# robocon_main_board_2017_rev3.net
KiCad netlist of a schematic drawn in EAGLE
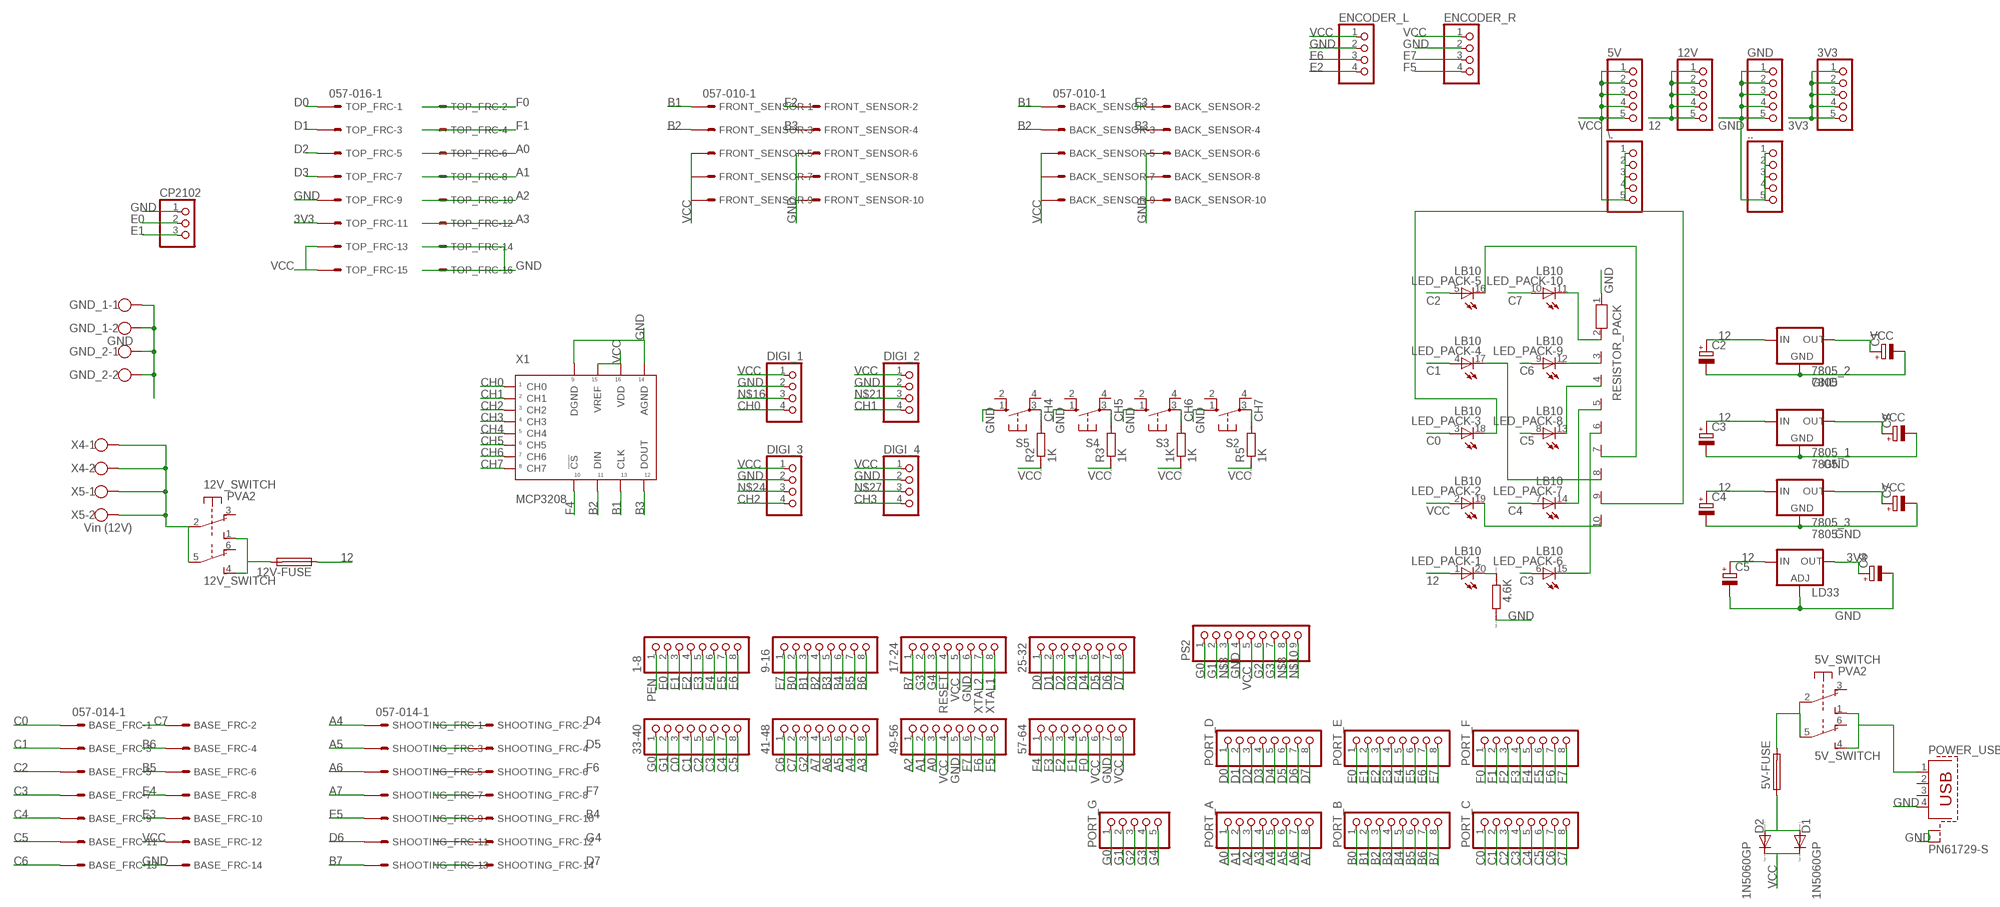
[diagram p0: schematic, sheet 1]

(export (version "E")
  (design (tool "Eeschema 10.0.6"))
  (components
    (comp (ref "..")
      (value "PINHD-1X5")
      (footprint "eagle-import:1X05")
      (libsource (lib "eagle-import") (part "PINHD-1X5"))
    )
    (comp (ref "1-8")
      (value "PINHD-1X8")
      (footprint "eagle-import:1X08")
      (libsource (lib "eagle-import") (part "PINHD-1X8"))
    )
    (comp (ref "1K")
      (value "1K")
      (footprint "eagle-import:0204_7")
      (libsource (lib "eagle-import") (part "R0204/7"))
    )
    (comp (ref "3V3")
      (value "PINHD-1X5")
      (footprint "eagle-import:1X05")
      (libsource (lib "eagle-import") (part "PINHD-1X5"))
    )
    (comp (ref "4.6K")
      (value "R0204/7")
      (footprint "eagle-import:0204_7")
      (libsource (lib "eagle-import") (part "R0204/7"))
    )
    (comp (ref "5V")
      (value "PINHD-1X5")
      (footprint "eagle-import:1X05")
      (libsource (lib "eagle-import") (part "PINHD-1X5"))
    )
    (comp (ref "5V-FUSE")
      (value "SH25")
      (footprint "eagle-import:SH25")
      (fields (field (name "MF") "SCHURTER") (field (name "MPN") "0031.8211"))
      (libsource (lib "eagle-import") (part "SH25"))
    )
    (comp (ref "5V_SWITCH")
      (value "PVA2")
      (footprint "eagle-import:PVA2F")
      (libsource (lib "eagle-import") (part "PVA2"))
    )
    (comp (ref "9-16")
      (value "PINHD-1X8")
      (footprint "eagle-import:1X08")
      (libsource (lib "eagle-import") (part "PINHD-1X8"))
    )
    (comp (ref "12V")
      (value "PINHD-1X5")
      (footprint "eagle-import:1X05")
      (libsource (lib "eagle-import") (part "PINHD-1X5"))
    )
    (comp (ref "12V-FUSE")
      (value "SH25")
      (footprint "eagle-import:SH25")
      (fields (field (name "MF") "SCHURTER") (field (name "MPN") "0031.8211"))
      (libsource (lib "eagle-import") (part "SH25"))
    )
    (comp (ref "12V_SWITCH")
      (value "PVA2")
      (footprint "eagle-import:PVA2F")
      (libsource (lib "eagle-import") (part "PVA2"))
    )
    (comp (ref "17-24")
      (value "PINHD-1X8")
      (footprint "eagle-import:1X08")
      (libsource (lib "eagle-import") (part "PINHD-1X8"))
    )
    (comp (ref "25-32")
      (value "PINHD-1X8")
      (footprint "eagle-import:1X08")
      (libsource (lib "eagle-import") (part "PINHD-1X8"))
    )
    (comp (ref "33-40")
      (value "PINHD-1X8")
      (footprint "eagle-import:1X08")
      (libsource (lib "eagle-import") (part "PINHD-1X8"))
    )
    (comp (ref "41-48")
      (value "PINHD-1X8")
      (footprint "eagle-import:1X08")
      (libsource (lib "eagle-import") (part "PINHD-1X8"))
    )
    (comp (ref "49-56")
      (value "PINHD-1X8")
      (footprint "eagle-import:1X08")
      (libsource (lib "eagle-import") (part "PINHD-1X8"))
    )
    (comp (ref "57-64")
      (value "PINHD-1X8")
      (footprint "eagle-import:1X08")
      (libsource (lib "eagle-import") (part "PINHD-1X8"))
    )
    (comp (ref "7805_1")
      (value "7805")
      (footprint "eagle-import:78XXS")
      (libsource (lib "eagle-import") (part "78XXS"))
    )
    (comp (ref "7805_2")
      (value "7805")
      (footprint "eagle-import:78XXS")
      (libsource (lib "eagle-import") (part "78XXS"))
    )
    (comp (ref "7805_3")
      (value "7805")
      (footprint "eagle-import:78XXS")
      (libsource (lib "eagle-import") (part "78XXS"))
    )
    (comp (ref "BACK_SENSOR")
      (value "057-010-1")
      (footprint "eagle-import:057-010-1")
      (libsource (lib "eagle-import") (part "057-010-1"))
    )
    (comp (ref "BASE_FRC")
      (value "057-014-1")
      (footprint "eagle-import:057-014-1")
      (libsource (lib "eagle-import") (part "057-014-1"))
    )
    (comp (ref "C1")
      (value "CPOL-EUE2.5-5")
      (footprint "eagle-import:E2,5-5")
      (libsource (lib "eagle-import") (part "CPOL-EUE2.5-5"))
    )
    (comp (ref "C2")
      (value "CPOL-EUE2.5-5")
      (footprint "eagle-import:E2,5-5")
      (libsource (lib "eagle-import") (part "CPOL-EUE2.5-5"))
    )
    (comp (ref "C3")
      (value "CPOL-EUE2.5-5")
      (footprint "eagle-import:E2,5-5")
      (libsource (lib "eagle-import") (part "CPOL-EUE2.5-5"))
    )
    (comp (ref "C4")
      (value "CPOL-EUE2.5-5")
      (footprint "eagle-import:E2,5-5")
      (libsource (lib "eagle-import") (part "CPOL-EUE2.5-5"))
    )
    (comp (ref "C5")
      (value "CPOL-EUE2.5-5")
      (footprint "eagle-import:E2,5-5")
      (libsource (lib "eagle-import") (part "CPOL-EUE2.5-5"))
    )
    (comp (ref "C6")
      (value "CPOL-EUE2.5-5")
      (footprint "eagle-import:E2,5-5")
      (libsource (lib "eagle-import") (part "CPOL-EUE2.5-5"))
    )
    (comp (ref "C7")
      (value "CPOL-EUE2.5-5")
      (footprint "eagle-import:E2,5-5")
      (libsource (lib "eagle-import") (part "CPOL-EUE2.5-5"))
    )
    (comp (ref "C8")
      (value "CPOL-EUE2.5-5")
      (footprint "eagle-import:E2,5-5")
      (libsource (lib "eagle-import") (part "CPOL-EUE2.5-5"))
    )
    (comp (ref "CP2102")
      (value "PINHD-1X3")
      (footprint "eagle-import:1X03")
      (libsource (lib "eagle-import") (part "PINHD-1X3"))
    )
    (comp (ref "D1")
      (value "1N5060GP")
      (footprint "eagle-import:DO15-12")
      (libsource (lib "eagle-import") (part "1N5060GP"))
    )
    (comp (ref "D2")
      (value "1N5060GP")
      (footprint "eagle-import:DO15-12")
      (libsource (lib "eagle-import") (part "1N5060GP"))
    )
    (comp (ref "DIGI_1")
      (value "PINHD-1X4")
      (footprint "eagle-import:1X04")
      (libsource (lib "eagle-import") (part "PINHD-1X4"))
    )
    (comp (ref "DIGI_2")
      (value "PINHD-1X4")
      (footprint "eagle-import:1X04")
      (libsource (lib "eagle-import") (part "PINHD-1X4"))
    )
    (comp (ref "DIGI_3")
      (value "PINHD-1X4")
      (footprint "eagle-import:1X04")
      (libsource (lib "eagle-import") (part "PINHD-1X4"))
    )
    (comp (ref "DIGI_4")
      (value "PINHD-1X4")
      (footprint "eagle-import:1X04")
      (libsource (lib "eagle-import") (part "PINHD-1X4"))
    )
    (comp (ref "ENCODER_L")
      (value "PINHD-1X4")
      (footprint "eagle-import:1X04")
      (libsource (lib "eagle-import") (part "PINHD-1X4"))
    )
    (comp (ref "ENCODER_R")
      (value "PINHD-1X4")
      (footprint "eagle-import:1X04")
      (libsource (lib "eagle-import") (part "PINHD-1X4"))
    )
    (comp (ref "FRONT_SENSOR")
      (value "057-010-1")
      (footprint "eagle-import:057-010-1")
      (libsource (lib "eagle-import") (part "057-010-1"))
    )
    (comp (ref "GND")
      (value "PINHD-1X5")
      (footprint "eagle-import:1X05")
      (libsource (lib "eagle-import") (part "PINHD-1X5"))
    )
    (comp (ref "GND_1")
      (value "GND")
      (footprint "eagle-import:W237-102")
      (fields (field (name "MPN") "237-102"))
      (libsource (lib "eagle-import") (part "W237-102"))
    )
    (comp (ref "GND_2")
      (value "W237-102")
      (footprint "eagle-import:W237-102")
      (fields (field (name "MPN") "237-102"))
      (libsource (lib "eagle-import") (part "W237-102"))
    )
    (comp (ref "LD33")
      (value "LM317TS")
      (footprint "eagle-import:317TS")
      (libsource (lib "eagle-import") (part "LM317TS"))
    )
    (comp (ref "LED_PACK")
      (value "LB10")
      (footprint "eagle-import:LB10")
      (libsource (lib "eagle-import") (part "LB10"))
    )
    (comp (ref "PORT_A")
      (value "PINHD-1X8")
      (footprint "eagle-import:1X08")
      (libsource (lib "eagle-import") (part "PINHD-1X8"))
    )
    (comp (ref "PORT_B")
      (value "PINHD-1X8")
      (footprint "eagle-import:1X08")
      (libsource (lib "eagle-import") (part "PINHD-1X8"))
    )
    (comp (ref "PORT_C")
      (value "PINHD-1X8")
      (footprint "eagle-import:1X08")
      (libsource (lib "eagle-import") (part "PINHD-1X8"))
    )
    (comp (ref "PORT_D")
      (value "PINHD-1X8")
      (footprint "eagle-import:1X08")
      (libsource (lib "eagle-import") (part "PINHD-1X8"))
    )
    (comp (ref "PORT_E")
      (value "PINHD-1X8")
      (footprint "eagle-import:1X08")
      (libsource (lib "eagle-import") (part "PINHD-1X8"))
    )
    (comp (ref "PORT_F")
      (value "PINHD-1X8")
      (footprint "eagle-import:1X08")
      (libsource (lib "eagle-import") (part "PINHD-1X8"))
    )
    (comp (ref "PORT_G")
      (value "PINHD-1X5")
      (footprint "eagle-import:1X05")
      (libsource (lib "eagle-import") (part "PINHD-1X5"))
    )
    (comp (ref "POWER_USB")
      (value "PN61729-S")
      (footprint "eagle-import:PN61729-S")
      (libsource (lib "eagle-import") (part "PN61729-S"))
    )
    (comp (ref "PS2")
      (value "PINHD-1X9")
      (footprint "eagle-import:1X09")
      (libsource (lib "eagle-import") (part "PINHD-1X9"))
    )
    (comp (ref "R2")
      (value "1K")
      (footprint "eagle-import:0204_7")
      (libsource (lib "eagle-import") (part "R0204/7"))
    )
    (comp (ref "R3")
      (value "1K")
      (footprint "eagle-import:0204_7")
      (libsource (lib "eagle-import") (part "R0204/7"))
    )
    (comp (ref "R5")
      (value "1K")
      (footprint "eagle-import:0204_7")
      (libsource (lib "eagle-import") (part "R0204/7"))
    )
    (comp (ref "RESISTOR_PACK")
      (value "RN09")
      (footprint "eagle-import:RN-10")
      (libsource (lib "eagle-import") (part "RN09"))
    )
    (comp (ref "S2")
      (value "10-XX")
      (footprint "eagle-import:B3F-10XX")
      (fields (field (name "MPN") "B3F-1000"))
      (libsource (lib "eagle-import") (part "10-XX"))
    )
    (comp (ref "S3")
      (value "10-XX")
      (footprint "eagle-import:B3F-10XX")
      (fields (field (name "MPN") "B3F-1000"))
      (libsource (lib "eagle-import") (part "10-XX"))
    )
    (comp (ref "S4")
      (value "10-XX")
      (footprint "eagle-import:B3F-10XX")
      (fields (field (name "MPN") "B3F-1000"))
      (libsource (lib "eagle-import") (part "10-XX"))
    )
    (comp (ref "S5")
      (value "10-XX")
      (footprint "eagle-import:B3F-10XX")
      (fields (field (name "MPN") "B3F-1000"))
      (libsource (lib "eagle-import") (part "10-XX"))
    )
    (comp (ref "SHOOTING_FRC")
      (value "057-014-1")
      (footprint "eagle-import:057-014-1")
      (libsource (lib "eagle-import") (part "057-014-1"))
    )
    (comp (ref "TOP_FRC")
      (value "057-016-1")
      (footprint "eagle-import:057-016-1")
      (libsource (lib "eagle-import") (part "057-016-1"))
    )
    (comp (ref "X1")
      (value "MCP3208")
      (footprint "eagle-import:DIP16")
      (libsource (lib "eagle-import") (part "21298EDIP"))
    )
    (comp (ref "X4")
      (value "W237-102")
      (footprint "eagle-import:W237-102")
      (fields (field (name "MPN") "237-102"))
      (libsource (lib "eagle-import") (part "W237-102"))
    )
    (comp (ref "X5")
      (value "Vin (12V)")
      (footprint "eagle-import:W237-102")
      (fields (field (name "MPN") "237-102"))
      (libsource (lib "eagle-import") (part "W237-102"))
    )
    (comp (ref "\\.")
      (value "PINHD-1X5")
      (footprint "eagle-import:1X05")
      (libsource (lib "eagle-import") (part "PINHD-1X5"))
    )
  )
  (nets
    (net (code "1") (name "/3V3") (class "Default")
      (node (ref "3V3") (pin "1") (pinfunction "1_1") (pintype "passive"))
      (node (ref "3V3") (pin "2") (pinfunction "2_2") (pintype "passive"))
      (node (ref "3V3") (pin "3") (pinfunction "3_3") (pintype "passive"))
      (node (ref "3V3") (pin "4") (pinfunction "4_4") (pintype "passive"))
      (node (ref "3V3") (pin "5") (pinfunction "5_5") (pintype "passive"))
      (node (ref "C6") (pin "+") (pinfunction "+_+") (pintype "passive"))
      (node (ref "LD33") (pin "2") (pinfunction "OUT_2") (pintype "passive"))
      (node (ref "TOP_FRC") (pin "11") (pinfunction "S_11") (pintype "passive"))
    )
    (net (code "2") (name "/12") (class "Default")
      (node (ref "12V") (pin "1") (pinfunction "1_1") (pintype "passive"))
      (node (ref "12V") (pin "2") (pinfunction "2_2") (pintype "passive"))
      (node (ref "12V") (pin "3") (pinfunction "3_3") (pintype "passive"))
      (node (ref "12V") (pin "4") (pinfunction "4_4") (pintype "passive"))
      (node (ref "12V") (pin "5") (pinfunction "5_5") (pintype "passive"))
      (node (ref "12V-FUSE") (pin "1") (pinfunction "1_1") (pintype "passive"))
      (node (ref "7805_1") (pin "IN") (pinfunction "IN_IN") (pintype "input"))
      (node (ref "7805_2") (pin "IN") (pinfunction "IN_IN") (pintype "input"))
      (node (ref "7805_3") (pin "IN") (pinfunction "IN_IN") (pintype "input"))
      (node (ref "C2") (pin "+") (pinfunction "+_+") (pintype "passive"))
      (node (ref "C3") (pin "+") (pinfunction "+_+") (pintype "passive"))
      (node (ref "C4") (pin "+") (pinfunction "+_+") (pintype "passive"))
      (node (ref "C5") (pin "+") (pinfunction "+_+") (pintype "passive"))
      (node (ref "LD33") (pin "3") (pinfunction "IN_3") (pintype "input"))
      (node (ref "LED_PACK") (pin "1") (pinfunction "A_1") (pintype "passive"))
    )
    (net (code "3") (name "/A0") (class "Default")
      (node (ref "49-56") (pin "3") (pinfunction "3_3") (pintype "passive"))
      (node (ref "PORT_A") (pin "1") (pinfunction "1_1") (pintype "passive"))
      (node (ref "TOP_FRC") (pin "6") (pinfunction "S_6") (pintype "passive"))
    )
    (net (code "4") (name "/A1") (class "Default")
      (node (ref "49-56") (pin "2") (pinfunction "2_2") (pintype "passive"))
      (node (ref "PORT_A") (pin "2") (pinfunction "2_2") (pintype "passive"))
      (node (ref "TOP_FRC") (pin "8") (pinfunction "S_8") (pintype "passive"))
    )
    (net (code "5") (name "/A2") (class "Default")
      (node (ref "49-56") (pin "1") (pinfunction "1_1") (pintype "passive"))
      (node (ref "PORT_A") (pin "3") (pinfunction "3_3") (pintype "passive"))
      (node (ref "TOP_FRC") (pin "10") (pinfunction "S_10") (pintype "passive"))
    )
    (net (code "6") (name "/A3") (class "Default")
      (node (ref "41-48") (pin "8") (pinfunction "8_8") (pintype "passive"))
      (node (ref "PORT_A") (pin "4") (pinfunction "4_4") (pintype "passive"))
      (node (ref "TOP_FRC") (pin "12") (pinfunction "S_12") (pintype "passive"))
    )
    (net (code "7") (name "/A4") (class "Default")
      (node (ref "41-48") (pin "7") (pinfunction "7_7") (pintype "passive"))
      (node (ref "PORT_A") (pin "5") (pinfunction "5_5") (pintype "passive"))
      (node (ref "SHOOTING_FRC") (pin "1") (pinfunction "S_1") (pintype "passive"))
    )
    (net (code "8") (name "/A5") (class "Default")
      (node (ref "41-48") (pin "6") (pinfunction "6_6") (pintype "passive"))
      (node (ref "PORT_A") (pin "6") (pinfunction "6_6") (pintype "passive"))
      (node (ref "SHOOTING_FRC") (pin "3") (pinfunction "S_3") (pintype "passive"))
    )
    (net (code "9") (name "/A6") (class "Default")
      (node (ref "41-48") (pin "5") (pinfunction "5_5") (pintype "passive"))
      (node (ref "PORT_A") (pin "7") (pinfunction "7_7") (pintype "passive"))
      (node (ref "SHOOTING_FRC") (pin "5") (pinfunction "S_5") (pintype "passive"))
    )
    (net (code "10") (name "/A7") (class "Default")
      (node (ref "41-48") (pin "4") (pinfunction "4_4") (pintype "passive"))
      (node (ref "PORT_A") (pin "8") (pinfunction "8_8") (pintype "passive"))
      (node (ref "SHOOTING_FRC") (pin "7") (pinfunction "S_7") (pintype "passive"))
    )
    (net (code "11") (name "/B0") (class "Default")
      (node (ref "9-16") (pin "2") (pinfunction "2_2") (pintype "passive"))
      (node (ref "PORT_B") (pin "1") (pinfunction "1_1") (pintype "passive"))
    )
    (net (code "12") (name "/B1") (class "Default")
      (node (ref "9-16") (pin "3") (pinfunction "3_3") (pintype "passive"))
      (node (ref "BACK_SENSOR") (pin "1") (pinfunction "S_1") (pintype "passive"))
      (node (ref "FRONT_SENSOR") (pin "1") (pinfunction "S_1") (pintype "passive"))
      (node (ref "PORT_B") (pin "2") (pinfunction "2_2") (pintype "passive"))
      (node (ref "X1") (pin "P$13") (pinfunction "CLK_P$13") (pintype "bidirectional"))
    )
    (net (code "13") (name "/B2") (class "Default")
      (node (ref "9-16") (pin "4") (pinfunction "4_4") (pintype "passive"))
      (node (ref "BACK_SENSOR") (pin "3") (pinfunction "S_3") (pintype "passive"))
      (node (ref "FRONT_SENSOR") (pin "3") (pinfunction "S_3") (pintype "passive"))
      (node (ref "PORT_B") (pin "3") (pinfunction "3_3") (pintype "passive"))
      (node (ref "X1") (pin "P$11") (pinfunction "DIN_P$11") (pintype "bidirectional"))
    )
    (net (code "14") (name "/B3") (class "Default")
      (node (ref "9-16") (pin "5") (pinfunction "5_5") (pintype "passive"))
      (node (ref "BACK_SENSOR") (pin "4") (pinfunction "S_4") (pintype "passive"))
      (node (ref "FRONT_SENSOR") (pin "4") (pinfunction "S_4") (pintype "passive"))
      (node (ref "PORT_B") (pin "4") (pinfunction "4_4") (pintype "passive"))
      (node (ref "X1") (pin "P$12") (pinfunction "DOUT_P$12") (pintype "bidirectional"))
    )
    (net (code "15") (name "/B4") (class "Default")
      (node (ref "9-16") (pin "6") (pinfunction "6_6") (pintype "passive"))
      (node (ref "PORT_B") (pin "5") (pinfunction "5_5") (pintype "passive"))
      (node (ref "SHOOTING_FRC") (pin "10") (pinfunction "S_10") (pintype "passive"))
    )
    (net (code "16") (name "/B5") (class "Default")
      (node (ref "9-16") (pin "7") (pinfunction "7_7") (pintype "passive"))
      (node (ref "BASE_FRC") (pin "6") (pinfunction "S_6") (pintype "passive"))
      (node (ref "PORT_B") (pin "6") (pinfunction "6_6") (pintype "passive"))
    )
    (net (code "17") (name "/B6") (class "Default")
      (node (ref "9-16") (pin "8") (pinfunction "8_8") (pintype "passive"))
      (node (ref "BASE_FRC") (pin "4") (pinfunction "S_4") (pintype "passive"))
      (node (ref "PORT_B") (pin "7") (pinfunction "7_7") (pintype "passive"))
    )
    (net (code "18") (name "/B7") (class "Default")
      (node (ref "17-24") (pin "1") (pinfunction "1_1") (pintype "passive"))
      (node (ref "PORT_B") (pin "8") (pinfunction "8_8") (pintype "passive"))
      (node (ref "SHOOTING_FRC") (pin "13") (pinfunction "S_13") (pintype "passive"))
    )
    (net (code "19") (name "/C0") (class "Default")
      (node (ref "33-40") (pin "3") (pinfunction "3_3") (pintype "passive"))
      (node (ref "BASE_FRC") (pin "1") (pinfunction "S_1") (pintype "passive"))
      (node (ref "LED_PACK") (pin "3") (pinfunction "A_3") (pintype "passive"))
      (node (ref "PORT_C") (pin "1") (pinfunction "1_1") (pintype "passive"))
    )
    (net (code "20") (name "/C1") (class "Default")
      (node (ref "33-40") (pin "4") (pinfunction "4_4") (pintype "passive"))
      (node (ref "BASE_FRC") (pin "3") (pinfunction "S_3") (pintype "passive"))
      (node (ref "LED_PACK") (pin "4") (pinfunction "A_4") (pintype "passive"))
      (node (ref "PORT_C") (pin "2") (pinfunction "2_2") (pintype "passive"))
    )
    (net (code "21") (name "/C2") (class "Default")
      (node (ref "33-40") (pin "5") (pinfunction "5_5") (pintype "passive"))
      (node (ref "BASE_FRC") (pin "5") (pinfunction "S_5") (pintype "passive"))
      (node (ref "LED_PACK") (pin "5") (pinfunction "A_5") (pintype "passive"))
      (node (ref "PORT_C") (pin "3") (pinfunction "3_3") (pintype "passive"))
    )
    (net (code "22") (name "/C3") (class "Default")
      (node (ref "33-40") (pin "6") (pinfunction "6_6") (pintype "passive"))
      (node (ref "BASE_FRC") (pin "7") (pinfunction "S_7") (pintype "passive"))
      (node (ref "LED_PACK") (pin "6") (pinfunction "A_6") (pintype "passive"))
      (node (ref "PORT_C") (pin "4") (pinfunction "4_4") (pintype "passive"))
    )
    (net (code "23") (name "/C4") (class "Default")
      (node (ref "33-40") (pin "7") (pinfunction "7_7") (pintype "passive"))
      (node (ref "BASE_FRC") (pin "9") (pinfunction "S_9") (pintype "passive"))
      (node (ref "LED_PACK") (pin "7") (pinfunction "A_7") (pintype "passive"))
      (node (ref "PORT_C") (pin "5") (pinfunction "5_5") (pintype "passive"))
    )
    (net (code "24") (name "/C5") (class "Default")
      (node (ref "33-40") (pin "8") (pinfunction "8_8") (pintype "passive"))
      (node (ref "BASE_FRC") (pin "11") (pinfunction "S_11") (pintype "passive"))
      (node (ref "LED_PACK") (pin "8") (pinfunction "A_8") (pintype "passive"))
      (node (ref "PORT_C") (pin "6") (pinfunction "6_6") (pintype "passive"))
    )
    (net (code "25") (name "/C6") (class "Default")
      (node (ref "41-48") (pin "1") (pinfunction "1_1") (pintype "passive"))
      (node (ref "BASE_FRC") (pin "13") (pinfunction "S_13") (pintype "passive"))
      (node (ref "LED_PACK") (pin "9") (pinfunction "A_9") (pintype "passive"))
      (node (ref "PORT_C") (pin "7") (pinfunction "7_7") (pintype "passive"))
    )
    (net (code "26") (name "/C7") (class "Default")
      (node (ref "41-48") (pin "2") (pinfunction "2_2") (pintype "passive"))
      (node (ref "BASE_FRC") (pin "2") (pinfunction "S_2") (pintype "passive"))
      (node (ref "LED_PACK") (pin "10") (pinfunction "A_10") (pintype "passive"))
      (node (ref "PORT_C") (pin "8") (pinfunction "8_8") (pintype "passive"))
    )
    (net (code "27") (name "/CH0") (class "Default")
      (node (ref "DIGI_1") (pin "4") (pinfunction "4_4") (pintype "passive"))
      (node (ref "X1") (pin "P$1") (pinfunction "CH0_P$1") (pintype "bidirectional"))
    )
    (net (code "28") (name "/CH1") (class "Default")
      (node (ref "DIGI_2") (pin "4") (pinfunction "4_4") (pintype "passive"))
      (node (ref "X1") (pin "P$2") (pinfunction "CH1_P$2") (pintype "bidirectional"))
    )
    (net (code "29") (name "/CH2") (class "Default")
      (node (ref "DIGI_3") (pin "4") (pinfunction "4_4") (pintype "passive"))
      (node (ref "X1") (pin "P$3") (pinfunction "CH2_P$3") (pintype "bidirectional"))
    )
    (net (code "30") (name "/CH3") (class "Default")
      (node (ref "DIGI_4") (pin "4") (pinfunction "4_4") (pintype "passive"))
      (node (ref "X1") (pin "P$4") (pinfunction "CH3_P$4") (pintype "bidirectional"))
    )
    (net (code "31") (name "/CH4") (class "Default")
      (node (ref "R2") (pin "2") (pinfunction "2_2") (pintype "passive"))
      (node (ref "S5") (pin "3") (pinfunction "P_3") (pintype "passive"))
      (node (ref "X1") (pin "P$5") (pinfunction "CH4_P$5") (pintype "bidirectional"))
    )
    (net (code "32") (name "/CH5") (class "Default")
      (node (ref "R3") (pin "2") (pinfunction "2_2") (pintype "passive"))
      (node (ref "S4") (pin "3") (pinfunction "P_3") (pintype "passive"))
      (node (ref "X1") (pin "P$6") (pinfunction "CH5_P$6") (pintype "bidirectional"))
    )
    (net (code "33") (name "/CH6") (class "Default")
      (node (ref "1K") (pin "2") (pinfunction "2_2") (pintype "passive"))
      (node (ref "S3") (pin "3") (pinfunction "P_3") (pintype "passive"))
      (node (ref "X1") (pin "P$7") (pinfunction "CH6_P$7") (pintype "bidirectional"))
    )
    (net (code "34") (name "/CH7") (class "Default")
      (node (ref "R5") (pin "2") (pinfunction "2_2") (pintype "passive"))
      (node (ref "S2") (pin "3") (pinfunction "P_3") (pintype "passive"))
      (node (ref "X1") (pin "P$8") (pinfunction "CH7_P$8") (pintype "bidirectional"))
    )
    (net (code "35") (name "/D0") (class "Default")
      (node (ref "25-32") (pin "1") (pinfunction "1_1") (pintype "passive"))
      (node (ref "PORT_D") (pin "1") (pinfunction "1_1") (pintype "passive"))
      (node (ref "TOP_FRC") (pin "1") (pinfunction "S_1") (pintype "passive"))
    )
    (net (code "36") (name "/D1") (class "Default")
      (node (ref "25-32") (pin "2") (pinfunction "2_2") (pintype "passive"))
      (node (ref "PORT_D") (pin "2") (pinfunction "2_2") (pintype "passive"))
      (node (ref "TOP_FRC") (pin "3") (pinfunction "S_3") (pintype "passive"))
    )
    (net (code "37") (name "/D2") (class "Default")
      (node (ref "25-32") (pin "3") (pinfunction "3_3") (pintype "passive"))
      (node (ref "PORT_D") (pin "3") (pinfunction "3_3") (pintype "passive"))
      (node (ref "TOP_FRC") (pin "5") (pinfunction "S_5") (pintype "passive"))
    )
    (net (code "38") (name "/D3") (class "Default")
      (node (ref "25-32") (pin "4") (pinfunction "4_4") (pintype "passive"))
      (node (ref "PORT_D") (pin "4") (pinfunction "4_4") (pintype "passive"))
      (node (ref "TOP_FRC") (pin "7") (pinfunction "S_7") (pintype "passive"))
    )
    (net (code "39") (name "/D4") (class "Default")
      (node (ref "25-32") (pin "5") (pinfunction "5_5") (pintype "passive"))
      (node (ref "PORT_D") (pin "5") (pinfunction "5_5") (pintype "passive"))
      (node (ref "SHOOTING_FRC") (pin "2") (pinfunction "S_2") (pintype "passive"))
    )
    (net (code "40") (name "/D5") (class "Default")
      (node (ref "25-32") (pin "6") (pinfunction "6_6") (pintype "passive"))
      (node (ref "PORT_D") (pin "6") (pinfunction "6_6") (pintype "passive"))
      (node (ref "SHOOTING_FRC") (pin "4") (pinfunction "S_4") (pintype "passive"))
    )
    (net (code "41") (name "/D6") (class "Default")
      (node (ref "25-32") (pin "7") (pinfunction "7_7") (pintype "passive"))
      (node (ref "PORT_D") (pin "7") (pinfunction "7_7") (pintype "passive"))
      (node (ref "SHOOTING_FRC") (pin "11") (pinfunction "S_11") (pintype "passive"))
    )
    (net (code "42") (name "/D7") (class "Default")
      (node (ref "25-32") (pin "8") (pinfunction "8_8") (pintype "passive"))
      (node (ref "PORT_D") (pin "8") (pinfunction "8_8") (pintype "passive"))
      (node (ref "SHOOTING_FRC") (pin "14") (pinfunction "S_14") (pintype "passive"))
    )
    (net (code "43") (name "/E0") (class "Default")
      (node (ref "1-8") (pin "2") (pinfunction "2_2") (pintype "passive"))
      (node (ref "CP2102") (pin "2") (pinfunction "2_2") (pintype "passive"))
      (node (ref "PORT_E") (pin "1") (pinfunction "1_1") (pintype "passive"))
    )
    (net (code "44") (name "/E1") (class "Default")
      (node (ref "1-8") (pin "3") (pinfunction "3_3") (pintype "passive"))
      (node (ref "CP2102") (pin "3") (pinfunction "3_3") (pintype "passive"))
      (node (ref "PORT_E") (pin "2") (pinfunction "2_2") (pintype "passive"))
    )
    (net (code "45") (name "/E2") (class "Default")
      (node (ref "1-8") (pin "4") (pinfunction "4_4") (pintype "passive"))
      (node (ref "ENCODER_L") (pin "4") (pinfunction "4_4") (pintype "passive"))
      (node (ref "PORT_E") (pin "3") (pinfunction "3_3") (pintype "passive"))
    )
    (net (code "46") (name "/E3") (class "Default")
      (node (ref "1-8") (pin "5") (pinfunction "5_5") (pintype "passive"))
      (node (ref "BASE_FRC") (pin "10") (pinfunction "S_10") (pintype "passive"))
      (node (ref "PORT_E") (pin "4") (pinfunction "4_4") (pintype "passive"))
    )
    (net (code "47") (name "/E4") (class "Default")
      (node (ref "1-8") (pin "6") (pinfunction "6_6") (pintype "passive"))
      (node (ref "BASE_FRC") (pin "8") (pinfunction "S_8") (pintype "passive"))
      (node (ref "PORT_E") (pin "5") (pinfunction "5_5") (pintype "passive"))
    )
    (net (code "48") (name "/E5") (class "Default")
      (node (ref "1-8") (pin "7") (pinfunction "7_7") (pintype "passive"))
      (node (ref "PORT_E") (pin "6") (pinfunction "6_6") (pintype "passive"))
      (node (ref "SHOOTING_FRC") (pin "9") (pinfunction "S_9") (pintype "passive"))
    )
    (net (code "49") (name "/E6") (class "Default")
      (node (ref "1-8") (pin "8") (pinfunction "8_8") (pintype "passive"))
      (node (ref "ENCODER_L") (pin "3") (pinfunction "3_3") (pintype "passive"))
      (node (ref "PORT_E") (pin "7") (pinfunction "7_7") (pintype "passive"))
    )
    (net (code "50") (name "/E7") (class "Default")
      (node (ref "9-16") (pin "1") (pinfunction "1_1") (pintype "passive"))
      (node (ref "ENCODER_R") (pin "3") (pinfunction "3_3") (pintype "passive"))
      (node (ref "PORT_E") (pin "8") (pinfunction "8_8") (pintype "passive"))
    )
    (net (code "51") (name "/F0") (class "Default")
      (node (ref "57-64") (pin "5") (pinfunction "5_5") (pintype "passive"))
      (node (ref "PORT_F") (pin "1") (pinfunction "1_1") (pintype "passive"))
      (node (ref "TOP_FRC") (pin "2") (pinfunction "S_2") (pintype "passive"))
    )
    (net (code "52") (name "/F1") (class "Default")
      (node (ref "57-64") (pin "4") (pinfunction "4_4") (pintype "passive"))
      (node (ref "PORT_F") (pin "2") (pinfunction "2_2") (pintype "passive"))
      (node (ref "TOP_FRC") (pin "4") (pinfunction "S_4") (pintype "passive"))
    )
    (net (code "53") (name "/F2") (class "Default")
      (node (ref "57-64") (pin "3") (pinfunction "3_3") (pintype "passive"))
      (node (ref "FRONT_SENSOR") (pin "2") (pinfunction "S_2") (pintype "passive"))
      (node (ref "PORT_F") (pin "3") (pinfunction "3_3") (pintype "passive"))
    )
    (net (code "54") (name "/F3") (class "Default")
      (node (ref "57-64") (pin "2") (pinfunction "2_2") (pintype "passive"))
      (node (ref "BACK_SENSOR") (pin "2") (pinfunction "S_2") (pintype "passive"))
      (node (ref "PORT_F") (pin "4") (pinfunction "4_4") (pintype "passive"))
    )
    (net (code "55") (name "/F4") (class "Default")
      (node (ref "57-64") (pin "1") (pinfunction "1_1") (pintype "passive"))
      (node (ref "PORT_F") (pin "5") (pinfunction "5_5") (pintype "passive"))
      (node (ref "X1") (pin "P$10") (pinfunction "~{CS}_P$10") (pintype "bidirectional"))
    )
    (net (code "56") (name "/F5") (class "Default")
      (node (ref "49-56") (pin "8") (pinfunction "8_8") (pintype "passive"))
      (node (ref "ENCODER_R") (pin "4") (pinfunction "4_4") (pintype "passive"))
      (node (ref "PORT_F") (pin "6") (pinfunction "6_6") (pintype "passive"))
    )
    (net (code "57") (name "/F6") (class "Default")
      (node (ref "49-56") (pin "7") (pinfunction "7_7") (pintype "passive"))
      (node (ref "PORT_F") (pin "7") (pinfunction "7_7") (pintype "passive"))
      (node (ref "SHOOTING_FRC") (pin "6") (pinfunction "S_6") (pintype "passive"))
    )
    (net (code "58") (name "/F7") (class "Default")
      (node (ref "49-56") (pin "6") (pinfunction "6_6") (pintype "passive"))
      (node (ref "PORT_F") (pin "8") (pinfunction "8_8") (pintype "passive"))
      (node (ref "SHOOTING_FRC") (pin "8") (pinfunction "S_8") (pintype "passive"))
    )
    (net (code "59") (name "/G0") (class "Default")
      (node (ref "33-40") (pin "1") (pinfunction "1_1") (pintype "passive"))
      (node (ref "PORT_G") (pin "1") (pinfunction "1_1") (pintype "passive"))
      (node (ref "PS2") (pin "1") (pinfunction "1_1") (pintype "passive"))
    )
    (net (code "60") (name "/G1") (class "Default")
      (node (ref "33-40") (pin "2") (pinfunction "2_2") (pintype "passive"))
      (node (ref "PORT_G") (pin "2") (pinfunction "2_2") (pintype "passive"))
      (node (ref "PS2") (pin "2") (pinfunction "2_2") (pintype "passive"))
    )
    (net (code "61") (name "/G2") (class "Default")
      (node (ref "41-48") (pin "3") (pinfunction "3_3") (pintype "passive"))
      (node (ref "PORT_G") (pin "3") (pinfunction "3_3") (pintype "passive"))
      (node (ref "PS2") (pin "6") (pinfunction "6_6") (pintype "passive"))
    )
    (net (code "62") (name "/G3") (class "Default")
      (node (ref "17-24") (pin "2") (pinfunction "2_2") (pintype "passive"))
      (node (ref "PORT_G") (pin "4") (pinfunction "4_4") (pintype "passive"))
      (node (ref "PS2") (pin "7") (pinfunction "7_7") (pintype "passive"))
    )
    (net (code "63") (name "/G4") (class "Default")
      (node (ref "17-24") (pin "3") (pinfunction "3_3") (pintype "passive"))
      (node (ref "PORT_G") (pin "5") (pinfunction "5_5") (pintype "passive"))
      (node (ref "SHOOTING_FRC") (pin "12") (pinfunction "S_12") (pintype "passive"))
    )
    (net (code "64") (name "/GND") (class "Default")
      (node (ref "..") (pin "1") (pinfunction "1_1") (pintype "passive"))
      (node (ref "..") (pin "2") (pinfunction "2_2") (pintype "passive"))
      (node (ref "..") (pin "3") (pinfunction "3_3") (pintype "passive"))
      (node (ref "..") (pin "4") (pinfunction "4_4") (pintype "passive"))
      (node (ref "..") (pin "5") (pinfunction "5_5") (pintype "passive"))
      (node (ref "17-24") (pin "6") (pinfunction "6_6") (pintype "passive"))
      (node (ref "4.6K") (pin "2") (pinfunction "2_2") (pintype "passive"))
      (node (ref "49-56") (pin "5") (pinfunction "5_5") (pintype "passive"))
      (node (ref "57-64") (pin "7") (pinfunction "7_7") (pintype "passive"))
      (node (ref "7805_1") (pin "GND") (pinfunction "GND_GND") (pintype "input"))
      (node (ref "7805_2") (pin "GND") (pinfunction "GND_GND") (pintype "input"))
      (node (ref "7805_3") (pin "GND") (pinfunction "GND_GND") (pintype "input"))
      (node (ref "BACK_SENSOR") (pin "10") (pinfunction "S_10") (pintype "passive"))
      (node (ref "BACK_SENSOR") (pin "6") (pinfunction "S_6") (pintype "passive"))
      (node (ref "BACK_SENSOR") (pin "8") (pinfunction "S_8") (pintype "passive"))
      (node (ref "BASE_FRC") (pin "14") (pinfunction "S_14") (pintype "passive"))
      (node (ref "C1") (pin "-") (pinfunction "-_-") (pintype "passive"))
      (node (ref "C2") (pin "-") (pinfunction "-_-") (pintype "passive"))
      (node (ref "C3") (pin "-") (pinfunction "-_-") (pintype "passive"))
      (node (ref "C4") (pin "-") (pinfunction "-_-") (pintype "passive"))
      (node (ref "C5") (pin "-") (pinfunction "-_-") (pintype "passive"))
      (node (ref "C6") (pin "-") (pinfunction "-_-") (pintype "passive"))
      (node (ref "C7") (pin "-") (pinfunction "-_-") (pintype "passive"))
      (node (ref "C8") (pin "-") (pinfunction "-_-") (pintype "passive"))
      (node (ref "CP2102") (pin "1") (pinfunction "1_1") (pintype "passive"))
      (node (ref "DIGI_1") (pin "2") (pinfunction "2_2") (pintype "passive"))
      (node (ref "DIGI_2") (pin "2") (pinfunction "2_2") (pintype "passive"))
      (node (ref "DIGI_3") (pin "2") (pinfunction "2_2") (pintype "passive"))
      (node (ref "DIGI_4") (pin "2") (pinfunction "2_2") (pintype "passive"))
      (node (ref "ENCODER_L") (pin "2") (pinfunction "2_2") (pintype "passive"))
      (node (ref "ENCODER_R") (pin "2") (pinfunction "2_2") (pintype "passive"))
      (node (ref "FRONT_SENSOR") (pin "10") (pinfunction "S_10") (pintype "passive"))
      (node (ref "FRONT_SENSOR") (pin "6") (pinfunction "S_6") (pintype "passive"))
      (node (ref "FRONT_SENSOR") (pin "8") (pinfunction "S_8") (pintype "passive"))
      (node (ref "GND") (pin "1") (pinfunction "1_1") (pintype "passive"))
      (node (ref "GND") (pin "2") (pinfunction "2_2") (pintype "passive"))
      (node (ref "GND") (pin "3") (pinfunction "3_3") (pintype "passive"))
      (node (ref "GND") (pin "4") (pinfunction "4_4") (pintype "passive"))
      (node (ref "GND") (pin "5") (pinfunction "5_5") (pintype "passive"))
      (node (ref "GND_1") (pin "1") (pinfunction "KL_1") (pintype "passive"))
      (node (ref "GND_1") (pin "2") (pinfunction "KL_2") (pintype "passive"))
      (node (ref "GND_2") (pin "1") (pinfunction "KL_1") (pintype "passive"))
      (node (ref "GND_2") (pin "2") (pinfunction "KL_2") (pintype "passive"))
      (node (ref "LD33") (pin "1") (pinfunction "ADJ_1") (pintype "input"))
      (node (ref "POWER_USB") (pin "4") (pinfunction "4_4") (pintype "passive"))
      (node (ref "POWER_USB") (pin "S1") (pinfunction "S1_S1") (pintype "passive"))
      (node (ref "POWER_USB") (pin "S2") (pinfunction "S2_S2") (pintype "passive"))
      (node (ref "PS2") (pin "4") (pinfunction "4_4") (pintype "passive"))
      (node (ref "RESISTOR_PACK") (pin "1") (pinfunction "1_1") (pintype "passive"))
      (node (ref "S2") (pin "1") (pinfunction "S_1") (pintype "passive"))
      (node (ref "S3") (pin "1") (pinfunction "S_1") (pintype "passive"))
      (node (ref "S4") (pin "1") (pinfunction "S_1") (pintype "passive"))
      (node (ref "S5") (pin "1") (pinfunction "S_1") (pintype "passive"))
      (node (ref "TOP_FRC") (pin "14") (pinfunction "S_14") (pintype "passive"))
      (node (ref "TOP_FRC") (pin "16") (pinfunction "S_16") (pintype "passive"))
      (node (ref "TOP_FRC") (pin "9") (pinfunction "S_9") (pintype "passive"))
      (node (ref "X1") (pin "P$14") (pinfunction "AGND_P$14") (pintype "bidirectional"))
      (node (ref "X1") (pin "P$9") (pinfunction "DGND_P$9") (pintype "bidirectional"))
    )
    (net (code "65") (name "/N$3") (class "Default")
      (node (ref "PS2") (pin "3") (pinfunction "3_3") (pintype "passive"))
    )
    (net (code "66") (name "/N$8") (class "Default")
      (node (ref "PS2") (pin "8") (pinfunction "8_8") (pintype "passive"))
    )
    (net (code "67") (name "/N$10") (class "Default")
      (node (ref "PS2") (pin "9") (pinfunction "9_9") (pintype "passive"))
    )
    (net (code "68") (name "/N$16") (class "Default")
      (node (ref "DIGI_1") (pin "3") (pinfunction "3_3") (pintype "passive"))
    )
    (net (code "69") (name "/N$21") (class "Default")
      (node (ref "DIGI_2") (pin "3") (pinfunction "3_3") (pintype "passive"))
    )
    (net (code "70") (name "/N$24") (class "Default")
      (node (ref "DIGI_3") (pin "3") (pinfunction "3_3") (pintype "passive"))
    )
    (net (code "71") (name "/N$27") (class "Default")
      (node (ref "DIGI_4") (pin "3") (pinfunction "3_3") (pintype "passive"))
    )
    (net (code "72") (name "/PEN") (class "Default")
      (node (ref "1-8") (pin "1") (pinfunction "1_1") (pintype "passive"))
    )
    (net (code "73") (name "/RESET") (class "Default")
      (node (ref "17-24") (pin "4") (pinfunction "4_4") (pintype "passive"))
    )
    (net (code "74") (name "/VCC") (class "Default")
      (node (ref "17-24") (pin "5") (pinfunction "5_5") (pintype "passive"))
      (node (ref "1K") (pin "1") (pinfunction "1_1") (pintype "passive"))
      (node (ref "49-56") (pin "4") (pinfunction "4_4") (pintype "passive"))
      (node (ref "57-64") (pin "6") (pinfunction "6_6") (pintype "passive"))
      (node (ref "57-64") (pin "8") (pinfunction "8_8") (pintype "passive"))
      (node (ref "5V") (pin "1") (pinfunction "1_1") (pintype "passive"))
      (node (ref "5V") (pin "2") (pinfunction "2_2") (pintype "passive"))
      (node (ref "5V") (pin "3") (pinfunction "3_3") (pintype "passive"))
      (node (ref "5V") (pin "4") (pinfunction "4_4") (pintype "passive"))
      (node (ref "5V") (pin "5") (pinfunction "5_5") (pintype "passive"))
      (node (ref "7805_1") (pin "OUT") (pinfunction "OUT_OUT") (pintype "passive"))
      (node (ref "7805_2") (pin "OUT") (pinfunction "OUT_OUT") (pintype "passive"))
      (node (ref "7805_3") (pin "OUT") (pinfunction "OUT_OUT") (pintype "passive"))
      (node (ref "BACK_SENSOR") (pin "5") (pinfunction "S_5") (pintype "passive"))
      (node (ref "BACK_SENSOR") (pin "7") (pinfunction "S_7") (pintype "passive"))
      (node (ref "BACK_SENSOR") (pin "9") (pinfunction "S_9") (pintype "passive"))
      (node (ref "BASE_FRC") (pin "12") (pinfunction "S_12") (pintype "passive"))
      (node (ref "C1") (pin "+") (pinfunction "+_+") (pintype "passive"))
      (node (ref "C7") (pin "+") (pinfunction "+_+") (pintype "passive"))
      (node (ref "C8") (pin "+") (pinfunction "+_+") (pintype "passive"))
      (node (ref "D1") (pin "C") (pinfunction "C_C") (pintype "passive"))
      (node (ref "D2") (pin "C") (pinfunction "C_C") (pintype "passive"))
      (node (ref "DIGI_1") (pin "1") (pinfunction "1_1") (pintype "passive"))
      (node (ref "DIGI_2") (pin "1") (pinfunction "1_1") (pintype "passive"))
      (node (ref "DIGI_3") (pin "1") (pinfunction "1_1") (pintype "passive"))
      (node (ref "DIGI_4") (pin "1") (pinfunction "1_1") (pintype "passive"))
      (node (ref "ENCODER_L") (pin "1") (pinfunction "1_1") (pintype "passive"))
      (node (ref "ENCODER_R") (pin "1") (pinfunction "1_1") (pintype "passive"))
      (node (ref "FRONT_SENSOR") (pin "5") (pinfunction "S_5") (pintype "passive"))
      (node (ref "FRONT_SENSOR") (pin "7") (pinfunction "S_7") (pintype "passive"))
      (node (ref "FRONT_SENSOR") (pin "9") (pinfunction "S_9") (pintype "passive"))
      (node (ref "LED_PACK") (pin "2") (pinfunction "A_2") (pintype "passive"))
      (node (ref "PS2") (pin "5") (pinfunction "5_5") (pintype "passive"))
      (node (ref "R2") (pin "1") (pinfunction "1_1") (pintype "passive"))
      (node (ref "R3") (pin "1") (pinfunction "1_1") (pintype "passive"))
      (node (ref "R5") (pin "1") (pinfunction "1_1") (pintype "passive"))
      (node (ref "TOP_FRC") (pin "13") (pinfunction "S_13") (pintype "passive"))
      (node (ref "TOP_FRC") (pin "15") (pinfunction "S_15") (pintype "passive"))
      (node (ref "X1") (pin "P$15") (pinfunction "VREF_P$15") (pintype "bidirectional"))
      (node (ref "X1") (pin "P$16") (pinfunction "VDD_P$16") (pintype "bidirectional"))
      (node (ref "\\.") (pin "1") (pinfunction "1_1") (pintype "passive"))
      (node (ref "\\.") (pin "2") (pinfunction "2_2") (pintype "passive"))
      (node (ref "\\.") (pin "3") (pinfunction "3_3") (pintype "passive"))
      (node (ref "\\.") (pin "4") (pinfunction "4_4") (pintype "passive"))
      (node (ref "\\.") (pin "5") (pinfunction "5_5") (pintype "passive"))
    )
    (net (code "75") (name "/XTAL1") (class "Default")
      (node (ref "17-24") (pin "8") (pinfunction "8_8") (pintype "passive"))
    )
    (net (code "76") (name "/XTAL2") (class "Default")
      (node (ref "17-24") (pin "7") (pinfunction "7_7") (pintype "passive"))
    )
    (net (code "77") (name "Net-(5V-FUSE-Pad1)") (class "Default")
      (node (ref "5V-FUSE") (pin "1") (pinfunction "1_1") (pintype "passive"))
      (node (ref "D1") (pin "A") (pinfunction "A_A") (pintype "passive"))
      (node (ref "D2") (pin "A") (pinfunction "A_A") (pintype "passive"))
    )
    (net (code "78") (name "Net-(5V_SWITCHA-P)") (class "Default")
      (node (ref "5V-FUSE") (pin "2") (pinfunction "2_2") (pintype "passive"))
      (node (ref "5V_SWITCH") (pin "2") (pinfunction "P_2") (pintype "passive"))
      (node (ref "5V_SWITCH") (pin "5") (pinfunction "P_5") (pintype "passive"))
    )
    (net (code "79") (name "Net-(5V_SWITCHA-S)") (class "Default")
      (node (ref "5V_SWITCH") (pin "1") (pinfunction "S_1") (pintype "passive"))
      (node (ref "5V_SWITCH") (pin "4") (pinfunction "S_4") (pintype "passive"))
      (node (ref "POWER_USB") (pin "1") (pinfunction "1_1") (pintype "passive"))
    )
    (net (code "80") (name "Net-(12V_SWITCHA-P)") (class "Default")
      (node (ref "12V_SWITCH") (pin "2") (pinfunction "P_2") (pintype "passive"))
      (node (ref "12V_SWITCH") (pin "5") (pinfunction "P_5") (pintype "passive"))
      (node (ref "X4") (pin "1") (pinfunction "KL_1") (pintype "passive"))
      (node (ref "X4") (pin "2") (pinfunction "KL_2") (pintype "passive"))
      (node (ref "X5") (pin "1") (pinfunction "KL_1") (pintype "passive"))
      (node (ref "X5") (pin "2") (pinfunction "KL_2") (pintype "passive"))
    )
    (net (code "81") (name "Net-(12V_SWITCHA-S)") (class "Default")
      (node (ref "12V-FUSE") (pin "2") (pinfunction "2_2") (pintype "passive"))
      (node (ref "12V_SWITCH") (pin "1") (pinfunction "S_1") (pintype "passive"))
      (node (ref "12V_SWITCH") (pin "4") (pinfunction "S_4") (pintype "passive"))
    )
    (net (code "82") (name "Net-(LED_PACKA-C)") (class "Default")
      (node (ref "4.6K") (pin "1") (pinfunction "1_1") (pintype "passive"))
      (node (ref "LED_PACK") (pin "20") (pinfunction "C_20") (pintype "passive"))
    )
    (net (code "83") (name "Net-(LED_PACKB-C)") (class "Default")
      (node (ref "LED_PACK") (pin "11") (pinfunction "C_11") (pintype "passive"))
      (node (ref "RESISTOR_PACK") (pin "2") (pinfunction "2_2") (pintype "passive"))
    )
    (net (code "84") (name "Net-(LED_PACKC-C)") (class "Default")
      (node (ref "LED_PACK") (pin "19") (pinfunction "C_19") (pintype "passive"))
      (node (ref "RESISTOR_PACK") (pin "10") (pinfunction "10_10") (pintype "passive"))
    )
    (net (code "85") (name "Net-(LED_PACKD-C)") (class "Default")
      (node (ref "LED_PACK") (pin "18") (pinfunction "C_18") (pintype "passive"))
      (node (ref "RESISTOR_PACK") (pin "9") (pinfunction "9_9") (pintype "passive"))
    )
    (net (code "86") (name "Net-(LED_PACKE-C)") (class "Default")
      (node (ref "LED_PACK") (pin "17") (pinfunction "C_17") (pintype "passive"))
      (node (ref "RESISTOR_PACK") (pin "8") (pinfunction "8_8") (pintype "passive"))
    )
    (net (code "87") (name "Net-(LED_PACKF-C)") (class "Default")
      (node (ref "LED_PACK") (pin "16") (pinfunction "C_16") (pintype "passive"))
      (node (ref "RESISTOR_PACK") (pin "7") (pinfunction "7_7") (pintype "passive"))
    )
    (net (code "88") (name "Net-(LED_PACKG-C)") (class "Default")
      (node (ref "LED_PACK") (pin "15") (pinfunction "C_15") (pintype "passive"))
      (node (ref "RESISTOR_PACK") (pin "6") (pinfunction "6_6") (pintype "passive"))
    )
    (net (code "89") (name "Net-(LED_PACKH-C)") (class "Default")
      (node (ref "LED_PACK") (pin "14") (pinfunction "C_14") (pintype "passive"))
      (node (ref "RESISTOR_PACK") (pin "5") (pinfunction "5_5") (pintype "passive"))
    )
    (net (code "90") (name "Net-(LED_PACKI-C)") (class "Default")
      (node (ref "LED_PACK") (pin "13") (pinfunction "C_13") (pintype "passive"))
      (node (ref "RESISTOR_PACK") (pin "4") (pinfunction "4_4") (pintype "passive"))
    )
    (net (code "91") (name "Net-(LED_PACKJ-C)") (class "Default")
      (node (ref "LED_PACK") (pin "12") (pinfunction "C_12") (pintype "passive"))
      (node (ref "RESISTOR_PACK") (pin "3") (pinfunction "3_3") (pintype "passive"))
    )
    (net (code "92") (name "unconnected-(5V_SWITCHA-O-Pad3)") (class "Default")
      (node (ref "5V_SWITCH") (pin "3") (pinfunction "O_3") (pintype "passive"))
    )
    (net (code "93") (name "unconnected-(5V_SWITCHB-O-Pad6)") (class "Default")
      (node (ref "5V_SWITCH") (pin "6") (pinfunction "O_6") (pintype "passive"))
    )
    (net (code "94") (name "unconnected-(12V_SWITCHA-O-Pad3)") (class "Default")
      (node (ref "12V_SWITCH") (pin "3") (pinfunction "O_3") (pintype "passive"))
    )
    (net (code "95") (name "unconnected-(12V_SWITCHB-O-Pad6)") (class "Default")
      (node (ref "12V_SWITCH") (pin "6") (pinfunction "O_6") (pintype "passive"))
    )
    (net (code "96") (name "unconnected-(POWER_USB-Pad2)") (class "Default")
      (node (ref "POWER_USB") (pin "2") (pinfunction "2_2") (pintype "passive"))
    )
    (net (code "97") (name "unconnected-(POWER_USB-Pad3)") (class "Default")
      (node (ref "POWER_USB") (pin "3") (pinfunction "3_3") (pintype "passive"))
    )
    (net (code "98") (name "unconnected-(S2-P1-Pad4)") (class "Default")
      (node (ref "S2") (pin "4") (pinfunction "P1_4") (pintype "passive"))
    )
    (net (code "99") (name "unconnected-(S2-S1-Pad2)") (class "Default")
      (node (ref "S2") (pin "2") (pinfunction "S1_2") (pintype "passive"))
    )
    (net (code "100") (name "unconnected-(S3-P1-Pad4)") (class "Default")
      (node (ref "S3") (pin "4") (pinfunction "P1_4") (pintype "passive"))
    )
    (net (code "101") (name "unconnected-(S3-S1-Pad2)") (class "Default")
      (node (ref "S3") (pin "2") (pinfunction "S1_2") (pintype "passive"))
    )
    (net (code "102") (name "unconnected-(S4-P1-Pad4)") (class "Default")
      (node (ref "S4") (pin "4") (pinfunction "P1_4") (pintype "passive"))
    )
    (net (code "103") (name "unconnected-(S4-S1-Pad2)") (class "Default")
      (node (ref "S4") (pin "2") (pinfunction "S1_2") (pintype "passive"))
    )
    (net (code "104") (name "unconnected-(S5-P1-Pad4)") (class "Default")
      (node (ref "S5") (pin "4") (pinfunction "P1_4") (pintype "passive"))
    )
    (net (code "105") (name "unconnected-(S5-S1-Pad2)") (class "Default")
      (node (ref "S5") (pin "2") (pinfunction "S1_2") (pintype "passive"))
    )
  )
)
